# space_charge.net
KiCad netlist of a schematic drawn in EAGLE
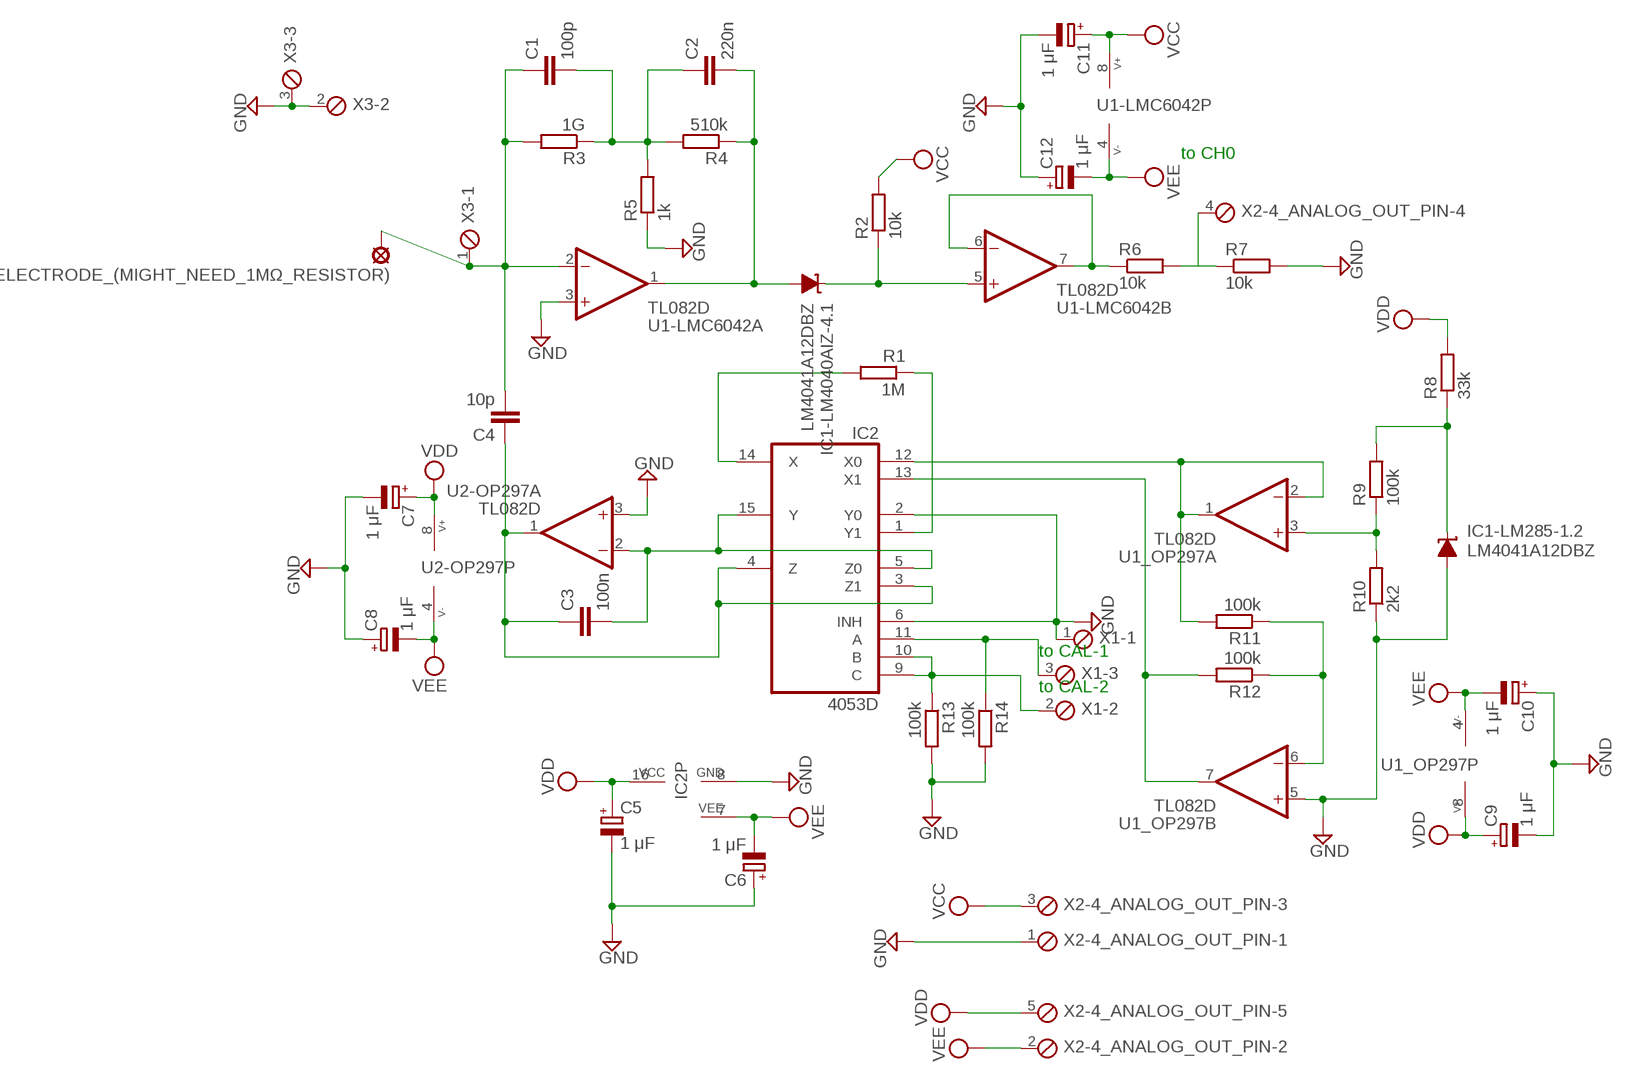
[diagram p0: schematic, sheet 1]

(export (version "E")
  (design (tool "Eeschema 10.0.6"))
  (components
    (comp (ref "C1")
      (value "100p")
      (footprint "eagle-import:C1206")
      (libsource (lib "eagle-import") (part "C-EUC1206"))
    )
    (comp (ref "C2")
      (value "220n")
      (footprint "eagle-import:C1206")
      (libsource (lib "eagle-import") (part "C-EUC1206"))
    )
    (comp (ref "C3")
      (value "100n")
      (footprint "eagle-import:C1206")
      (libsource (lib "eagle-import") (part "C-EUC1206"))
    )
    (comp (ref "C4")
      (value "10p")
      (footprint "eagle-import:C1206")
      (libsource (lib "eagle-import") (part "C-EUC1206"))
    )
    (comp (ref "C5")
      (value "1 μF")
      (footprint "eagle-import:A_3216-18R")
      (libsource (lib "eagle-import") (part "CPOL-EUA/3216-18R"))
    )
    (comp (ref "C6")
      (value "1 μF")
      (footprint "eagle-import:A_3216-18R")
      (libsource (lib "eagle-import") (part "CPOL-EUA/3216-18R"))
    )
    (comp (ref "C7")
      (value "1 μF")
      (footprint "eagle-import:A_3216-18R")
      (libsource (lib "eagle-import") (part "CPOL-EUA/3216-18R"))
    )
    (comp (ref "C8")
      (value "1 μF")
      (footprint "eagle-import:A_3216-18R")
      (libsource (lib "eagle-import") (part "CPOL-EUA/3216-18R"))
    )
    (comp (ref "C9")
      (value "1 μF")
      (footprint "eagle-import:A_3216-18R")
      (libsource (lib "eagle-import") (part "CPOL-EUA/3216-18R"))
    )
    (comp (ref "C10")
      (value "1 μF")
      (footprint "eagle-import:A_3216-18R")
      (libsource (lib "eagle-import") (part "CPOL-EUA/3216-18R"))
    )
    (comp (ref "C11")
      (value "1 μF")
      (footprint "eagle-import:A_3216-18R")
      (libsource (lib "eagle-import") (part "CPOL-EUA/3216-18R"))
    )
    (comp (ref "C12")
      (value "1 μF")
      (footprint "eagle-import:A_3216-18R")
      (libsource (lib "eagle-import") (part "CPOL-EUA/3216-18R"))
    )
    (comp (ref "IC1-LM285-1.2")
      (value "LM4041A12DBZ")
      (footprint "eagle-import:DBZ_R-PDSO-G3")
      (fields (field (name "MPN") "LM4041A12IDBZR"))
      (libsource (lib "eagle-import") (part "LM4041DBZA12"))
    )
    (comp (ref "IC1-LM4040AIZ-4.1")
      (value "LM4041A12DBZ")
      (footprint "eagle-import:DBZ_R-PDSO-G3")
      (fields (field (name "MPN") "LM4041A12IDBZR"))
      (libsource (lib "eagle-import") (part "LM4041DBZA12"))
    )
    (comp (ref "IC2")
      (value "4053D")
      (footprint "eagle-import:SO16")
      (libsource (lib "eagle-import") (part "4053D"))
    )
    (comp (ref "R1")
      (value "1M")
      (footprint "eagle-import:R1206")
      (libsource (lib "eagle-import") (part "R-EU_R1206"))
    )
    (comp (ref "R2")
      (value "10k")
      (footprint "eagle-import:R1206")
      (libsource (lib "eagle-import") (part "resistor_R-EU_R1206"))
    )
    (comp (ref "R3")
      (value "1G")
      (footprint "eagle-import:R1206")
      (libsource (lib "eagle-import") (part "resistor_R-EU_R1206"))
    )
    (comp (ref "R4")
      (value "510k")
      (footprint "eagle-import:R1206")
      (libsource (lib "eagle-import") (part "resistor_R-EU_R1206"))
    )
    (comp (ref "R5")
      (value "1k")
      (footprint "eagle-import:R1206")
      (libsource (lib "eagle-import") (part "resistor_R-EU_R1206"))
    )
    (comp (ref "R6")
      (value "10k")
      (footprint "eagle-import:R1206")
      (libsource (lib "eagle-import") (part "R-EU_R1206"))
    )
    (comp (ref "R7")
      (value "10k")
      (footprint "eagle-import:R1206")
      (libsource (lib "eagle-import") (part "R-EU_R1206"))
    )
    (comp (ref "R8")
      (value "33k")
      (footprint "eagle-import:R1206")
      (libsource (lib "eagle-import") (part "R-EU_R1206"))
    )
    (comp (ref "R9")
      (value "100k")
      (footprint "eagle-import:R1206")
      (libsource (lib "eagle-import") (part "R-EU_R1206"))
    )
    (comp (ref "R10")
      (value "2k2")
      (footprint "eagle-import:R1206")
      (libsource (lib "eagle-import") (part "R-EU_R1206"))
    )
    (comp (ref "R11")
      (value "100k")
      (footprint "eagle-import:R1206")
      (libsource (lib "eagle-import") (part "resistor_R-EU_R1206"))
    )
    (comp (ref "R12")
      (value "100k")
      (footprint "eagle-import:R1206")
      (libsource (lib "eagle-import") (part "resistor_R-EU_R1206"))
    )
    (comp (ref "R13")
      (value "100k")
      (footprint "eagle-import:R1206")
      (libsource (lib "eagle-import") (part "resistor_R-EU_R1206"))
    )
    (comp (ref "R14")
      (value "100k")
      (footprint "eagle-import:R1206")
      (libsource (lib "eagle-import") (part "resistor_R-EU_R1206"))
    )
    (comp (ref "TO_ELECTRODE_(MIGHT_NEED_1MΩ_RESISTOR)")
      (value "LSP10")
      (footprint "eagle-import:LSP10")
      (libsource (lib "eagle-import") (part "LSP10"))
    )
    (comp (ref "U1-LMC6042")
      (value "TL082D")
      (footprint "eagle-import:SO08")
      (libsource (lib "eagle-import") (part "TL082D"))
    )
    (comp (ref "U1_OP297")
      (value "TL082D")
      (footprint "eagle-import:SO08")
      (libsource (lib "eagle-import") (part "TL082D"))
    )
    (comp (ref "U2-OP297")
      (value "TL082D")
      (footprint "eagle-import:SO08")
      (libsource (lib "eagle-import") (part "TL082D"))
    )
    (comp (ref "X1")
      (value "MPT3")
      (footprint "eagle-import:3POL254")
      (libsource (lib "eagle-import") (part "MPT3"))
    )
    (comp (ref "X2-4_ANALOG_OUT_PIN")
      (value "MPT5")
      (footprint "eagle-import:5POL254")
      (libsource (lib "eagle-import") (part "MPT5"))
    )
    (comp (ref "X3")
      (value "MPT3")
      (footprint "eagle-import:3POL254")
      (libsource (lib "eagle-import") (part "MPT3"))
    )
  )
  (nets
    (net (code "1") (name "GND") (class "Default")
      (node (ref "C10") (pin "+") (pinfunction "+_+") (pintype "passive"))
      (node (ref "C11") (pin "-") (pinfunction "-_-") (pintype "passive"))
      (node (ref "C12") (pin "+") (pinfunction "+_+") (pintype "passive"))
      (node (ref "C5") (pin "-") (pinfunction "-_-") (pintype "passive"))
      (node (ref "C6") (pin "+") (pinfunction "+_+") (pintype "passive"))
      (node (ref "C7") (pin "-") (pinfunction "-_-") (pintype "passive"))
      (node (ref "C8") (pin "+") (pinfunction "+_+") (pintype "passive"))
      (node (ref "C9") (pin "-") (pinfunction "-_-") (pintype "passive"))
      (node (ref "IC1-LM285-1.2") (pin "2") (pinfunction "A_2") (pintype "passive"))
      (node (ref "IC2") (pin "2") (pinfunction "Y0_2") (pintype "bidirectional"))
      (node (ref "IC2") (pin "6") (pinfunction "INH_6") (pintype "input"))
      (node (ref "IC2") (pin "8") (pinfunction "GND_8") (pintype "power_in"))
      (node (ref "R10") (pin "1") (pinfunction "1_1") (pintype "passive"))
      (node (ref "R13") (pin "2") (pinfunction "2_2") (pintype "passive"))
      (node (ref "R14") (pin "2") (pinfunction "2_2") (pintype "passive"))
      (node (ref "R5") (pin "1") (pinfunction "1_1") (pintype "passive"))
      (node (ref "R7") (pin "2") (pinfunction "2_2") (pintype "passive"))
      (node (ref "U1-LMC6042") (pin "3") (pinfunction "+IN_3") (pintype "input"))
      (node (ref "U1_OP297") (pin "5") (pinfunction "+IN_5") (pintype "input"))
      (node (ref "U2-OP297") (pin "3") (pinfunction "+IN_3") (pintype "input"))
      (node (ref "X1") (pin "1") (pinfunction "1_1") (pintype "passive"))
      (node (ref "X2-4_ANALOG_OUT_PIN") (pin "1") (pinfunction "1_1") (pintype "passive"))
      (node (ref "X3") (pin "2") (pinfunction "1_2") (pintype "passive"))
      (node (ref "X3") (pin "3") (pinfunction "1_3") (pintype "passive"))
    )
    (net (code "2") (name "Net-(C1-Pad2)") (class "Default")
      (node (ref "C1") (pin "2") (pinfunction "2_2") (pintype "passive"))
      (node (ref "C2") (pin "1") (pinfunction "1_1") (pintype "passive"))
      (node (ref "R3") (pin "1") (pinfunction "1_1") (pintype "passive"))
      (node (ref "R4") (pin "2") (pinfunction "2_2") (pintype "passive"))
      (node (ref "R5") (pin "2") (pinfunction "2_2") (pintype "passive"))
    )
    (net (code "3") (name "Net-(IC1-LM285-1.2-C)") (class "Default")
      (node (ref "IC1-LM285-1.2") (pin "1") (pinfunction "C_1") (pintype "passive"))
      (node (ref "R8") (pin "1") (pinfunction "1_1") (pintype "passive"))
      (node (ref "R9") (pin "2") (pinfunction "2_2") (pintype "passive"))
    )
    (net (code "4") (name "Net-(IC1-LM4040AIZ-4.1-A)") (class "Default")
      (node (ref "C2") (pin "2") (pinfunction "2_2") (pintype "passive"))
      (node (ref "IC1-LM4040AIZ-4.1") (pin "2") (pinfunction "A_2") (pintype "passive"))
      (node (ref "R4") (pin "1") (pinfunction "1_1") (pintype "passive"))
      (node (ref "U1-LMC6042") (pin "1") (pinfunction "OUT_1") (pintype "output"))
    )
    (net (code "5") (name "Net-(IC1-LM4040AIZ-4.1-C)") (class "Default")
      (node (ref "IC1-LM4040AIZ-4.1") (pin "1") (pinfunction "C_1") (pintype "passive"))
      (node (ref "R2") (pin "1") (pinfunction "1_1") (pintype "passive"))
      (node (ref "U1-LMC6042") (pin "5") (pinfunction "+IN_5") (pintype "input"))
    )
    (net (code "6") (name "Net-(IC2A-A)") (class "Default")
      (node (ref "IC2") (pin "11") (pinfunction "A_11") (pintype "input"))
      (node (ref "R14") (pin "1") (pinfunction "1_1") (pintype "passive"))
      (node (ref "X1") (pin "3") (pinfunction "1_3") (pintype "passive"))
    )
    (net (code "7") (name "Net-(IC2A-B)") (class "Default")
      (node (ref "IC2") (pin "10") (pinfunction "B_10") (pintype "input"))
      (node (ref "IC2") (pin "9") (pinfunction "C_9") (pintype "input"))
      (node (ref "R13") (pin "1") (pinfunction "1_1") (pintype "passive"))
      (node (ref "X1") (pin "2") (pinfunction "1_2") (pintype "passive"))
    )
    (net (code "8") (name "Net-(IC2A-X)") (class "Default")
      (node (ref "IC2") (pin "14") (pinfunction "X_14") (pintype "bidirectional"))
      (node (ref "R1") (pin "2") (pinfunction "2_2") (pintype "passive"))
    )
    (net (code "9") (name "Net-(IC2A-X0)") (class "Default")
      (node (ref "IC2") (pin "12") (pinfunction "X0_12") (pintype "bidirectional"))
      (node (ref "R11") (pin "2") (pinfunction "2_2") (pintype "passive"))
      (node (ref "U1_OP297") (pin "1") (pinfunction "OUT_1") (pintype "output"))
      (node (ref "U1_OP297") (pin "2") (pinfunction "-IN_2") (pintype "input"))
    )
    (net (code "10") (name "Net-(IC2A-X1)") (class "Default")
      (node (ref "IC2") (pin "13") (pinfunction "X1_13") (pintype "bidirectional"))
      (node (ref "R12") (pin "2") (pinfunction "2_2") (pintype "passive"))
      (node (ref "U1_OP297") (pin "7") (pinfunction "OUT_7") (pintype "output"))
    )
    (net (code "11") (name "Net-(IC2A-Y)") (class "Default")
      (node (ref "C3") (pin "2") (pinfunction "2_2") (pintype "passive"))
      (node (ref "IC2") (pin "15") (pinfunction "Y_15") (pintype "bidirectional"))
      (node (ref "IC2") (pin "5") (pinfunction "Z0_5") (pintype "bidirectional"))
      (node (ref "U2-OP297") (pin "2") (pinfunction "-IN_2") (pintype "input"))
    )
    (net (code "12") (name "Net-(IC2A-Y1)") (class "Default")
      (node (ref "IC2") (pin "1") (pinfunction "Y1_1") (pintype "bidirectional"))
      (node (ref "R1") (pin "1") (pinfunction "1_1") (pintype "passive"))
    )
    (net (code "13") (name "Net-(IC2A-Z)") (class "Default")
      (node (ref "C3") (pin "1") (pinfunction "1_1") (pintype "passive"))
      (node (ref "C4") (pin "1") (pinfunction "1_1") (pintype "passive"))
      (node (ref "IC2") (pin "3") (pinfunction "Z1_3") (pintype "bidirectional"))
      (node (ref "IC2") (pin "4") (pinfunction "Z_4") (pintype "bidirectional"))
      (node (ref "U2-OP297") (pin "1") (pinfunction "OUT_1") (pintype "output"))
    )
    (net (code "14") (name "Net-(U1-LMC6042A--IN)") (class "Default")
      (node (ref "C1") (pin "1") (pinfunction "1_1") (pintype "passive"))
      (node (ref "C4") (pin "2") (pinfunction "2_2") (pintype "passive"))
      (node (ref "R3") (pin "2") (pinfunction "2_2") (pintype "passive"))
      (node (ref "TO_ELECTRODE_(MIGHT_NEED_1MΩ_RESISTOR)") (pin "MP") (pinfunction "MP_MP") (pintype "passive"))
      (node (ref "U1-LMC6042") (pin "2") (pinfunction "-IN_2") (pintype "input"))
      (node (ref "X3") (pin "1") (pinfunction "1_1") (pintype "passive"))
    )
    (net (code "15") (name "Net-(U1-LMC6042B--IN)") (class "Default")
      (node (ref "R6") (pin "1") (pinfunction "1_1") (pintype "passive"))
      (node (ref "U1-LMC6042") (pin "6") (pinfunction "-IN_6") (pintype "input"))
      (node (ref "U1-LMC6042") (pin "7") (pinfunction "OUT_7") (pintype "output"))
    )
    (net (code "16") (name "Net-(U1_OP297A-+IN)") (class "Default")
      (node (ref "R10") (pin "2") (pinfunction "2_2") (pintype "passive"))
      (node (ref "R9") (pin "1") (pinfunction "1_1") (pintype "passive"))
      (node (ref "U1_OP297") (pin "3") (pinfunction "+IN_3") (pintype "input"))
    )
    (net (code "17") (name "Net-(U1_OP297B--IN)") (class "Default")
      (node (ref "R11") (pin "1") (pinfunction "1_1") (pintype "passive"))
      (node (ref "R12") (pin "1") (pinfunction "1_1") (pintype "passive"))
      (node (ref "U1_OP297") (pin "6") (pinfunction "-IN_6") (pintype "input"))
    )
    (net (code "18") (name "Net-(X2-4_ANALOG_OUT_PIND-1)") (class "Default")
      (node (ref "R6") (pin "2") (pinfunction "2_2") (pintype "passive"))
      (node (ref "R7") (pin "1") (pinfunction "1_1") (pintype "passive"))
      (node (ref "X2-4_ANALOG_OUT_PIN") (pin "4") (pinfunction "1_4") (pintype "passive"))
    )
    (net (code "19") (name "VCC") (class "Default")
      (node (ref "C11") (pin "+") (pinfunction "+_+") (pintype "passive"))
      (node (ref "R2") (pin "2") (pinfunction "2_2") (pintype "passive"))
      (node (ref "U1-LMC6042") (pin "8") (pinfunction "V+_8") (pintype "power_in"))
      (node (ref "X2-4_ANALOG_OUT_PIN") (pin "3") (pinfunction "1_3") (pintype "passive"))
    )
    (net (code "20") (name "VDD") (class "Default")
      (node (ref "C5") (pin "+") (pinfunction "+_+") (pintype "passive"))
      (node (ref "C7") (pin "+") (pinfunction "+_+") (pintype "passive"))
      (node (ref "C9") (pin "+") (pinfunction "+_+") (pintype "passive"))
      (node (ref "IC2") (pin "16") (pinfunction "VCC_16") (pintype "power_in"))
      (node (ref "R8") (pin "2") (pinfunction "2_2") (pintype "passive"))
      (node (ref "U1_OP297") (pin "8") (pinfunction "V+_8") (pintype "power_in"))
      (node (ref "U2-OP297") (pin "8") (pinfunction "V+_8") (pintype "power_in"))
      (node (ref "X2-4_ANALOG_OUT_PIN") (pin "5") (pinfunction "1_5") (pintype "passive"))
    )
    (net (code "21") (name "VEE") (class "Default")
      (node (ref "C10") (pin "-") (pinfunction "-_-") (pintype "passive"))
      (node (ref "C12") (pin "-") (pinfunction "-_-") (pintype "passive"))
      (node (ref "C6") (pin "-") (pinfunction "-_-") (pintype "passive"))
      (node (ref "C8") (pin "-") (pinfunction "-_-") (pintype "passive"))
      (node (ref "IC2") (pin "7") (pinfunction "VEE_7") (pintype "power_in"))
      (node (ref "U1-LMC6042") (pin "4") (pinfunction "V-_4") (pintype "power_in"))
      (node (ref "U1_OP297") (pin "4") (pinfunction "V-_4") (pintype "power_in"))
      (node (ref "U2-OP297") (pin "4") (pinfunction "V-_4") (pintype "power_in"))
      (node (ref "X2-4_ANALOG_OUT_PIN") (pin "2") (pinfunction "1_2") (pintype "passive"))
    )
  )
)
